# Quad_Mosfet_Module.net
KiCad netlist of a schematic drawn in EAGLE
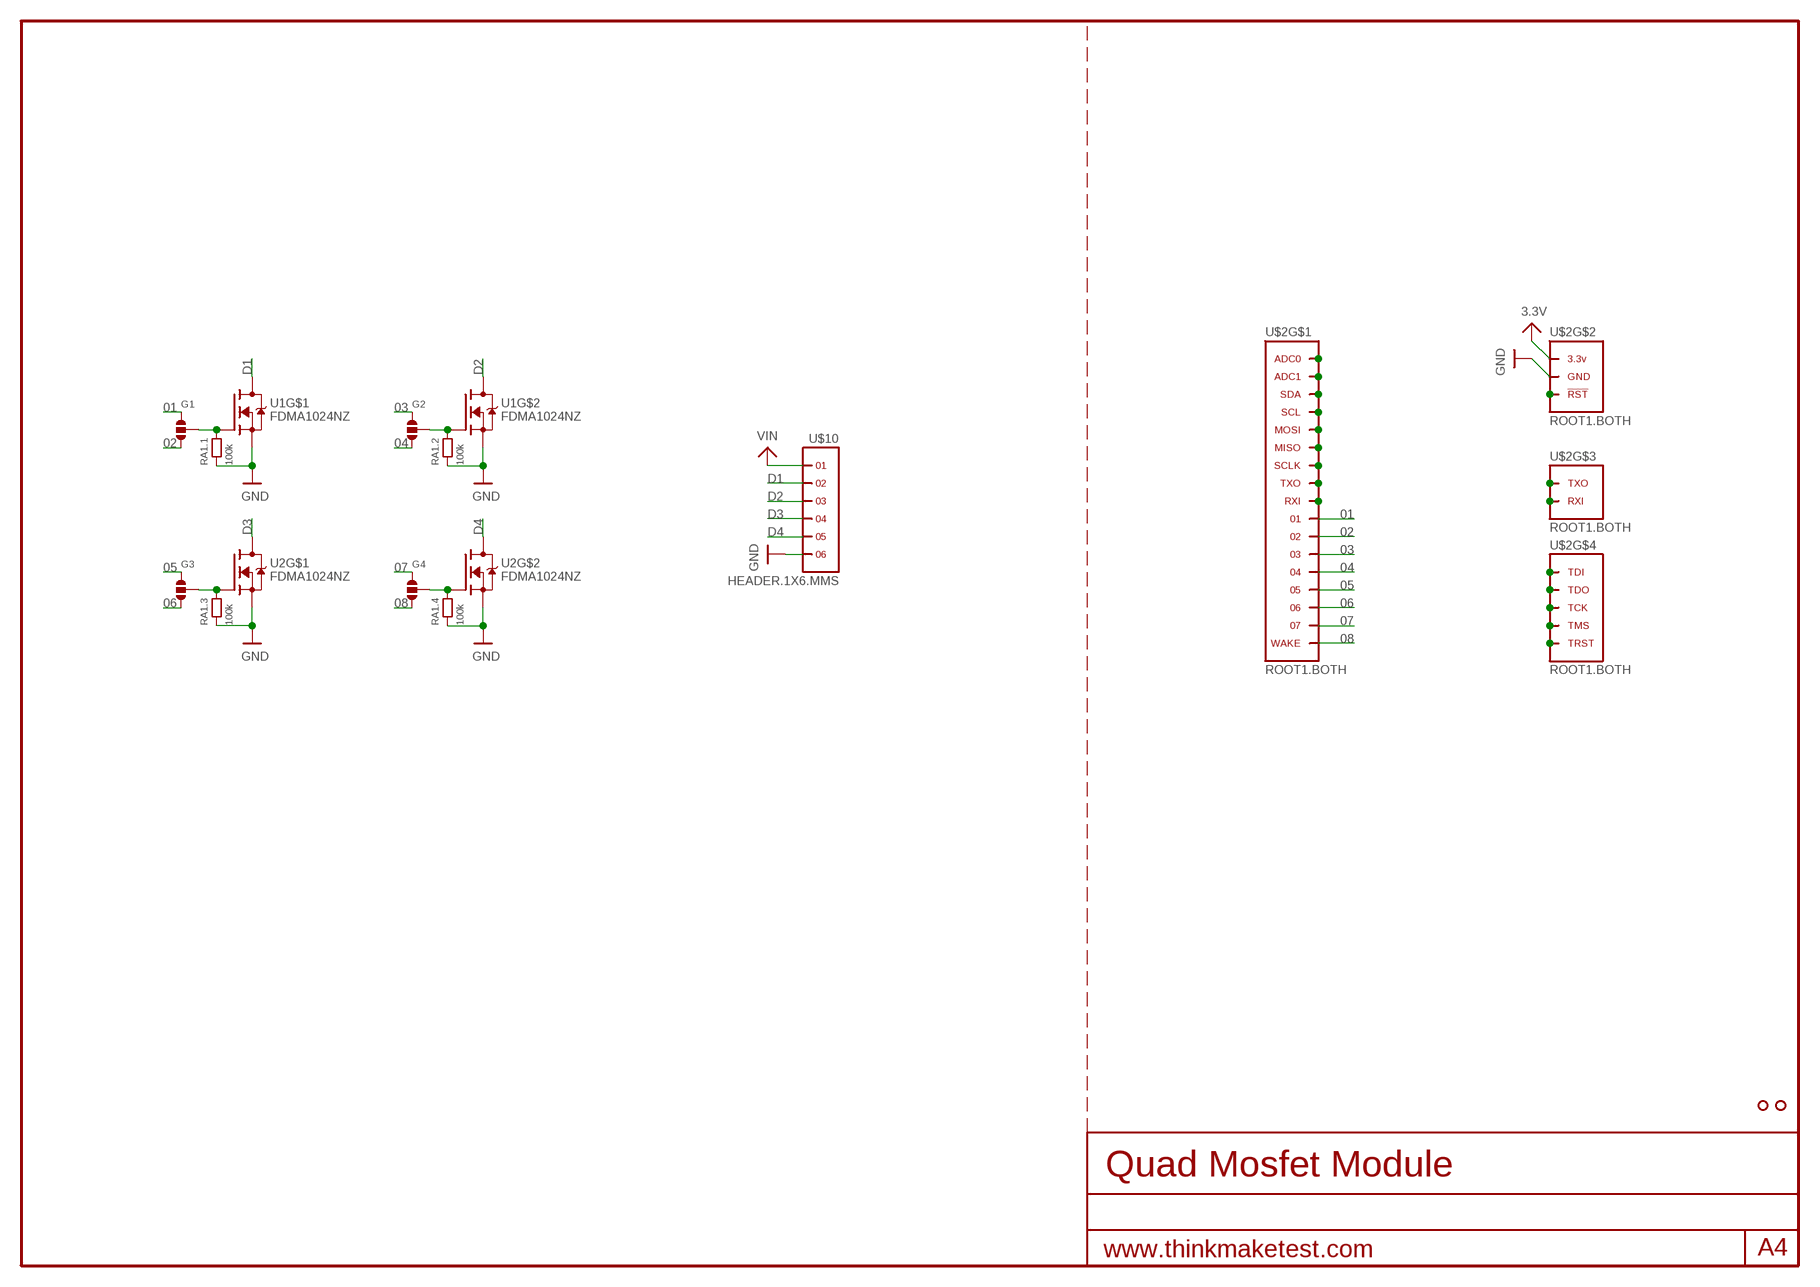
[diagram p0: schematic, sheet 1]

(export (version "E")
  (design (tool "Eeschema 10.0.6"))
  (components
    (comp (ref "G1")
      (value "SOLDERJUMPER.3.MED.12")
      (footprint "eagle-import:3.MED.12")
      (libsource (lib "eagle-import") (part "SOLDERJUMPER.3.MED.12"))
    )
    (comp (ref "G2")
      (value "SOLDERJUMPER.3.MED.12")
      (footprint "eagle-import:3.MED.12")
      (libsource (lib "eagle-import") (part "SOLDERJUMPER.3.MED.12"))
    )
    (comp (ref "G3")
      (value "SOLDERJUMPER.3.MED.12")
      (footprint "eagle-import:3.MED.12")
      (libsource (lib "eagle-import") (part "SOLDERJUMPER.3.MED.12"))
    )
    (comp (ref "G4")
      (value "SOLDERJUMPER.3.MED.12")
      (footprint "eagle-import:3.MED.12")
      (libsource (lib "eagle-import") (part "SOLDERJUMPER.3.MED.12"))
    )
    (comp (ref "RA1")
      (value "100k")
      (footprint "eagle-import:0603.4.C")
      (libsource (lib "eagle-import") (part "RA-4.0603"))
    )
    (comp (ref "U$2")
      (value "ROOT1.BOTH")
      (footprint "eagle-import:ROOT1.BOTH")
      (libsource (lib "eagle-import") (part "ROOT1.BOTH"))
    )
    (comp (ref "U$3")
      (value "HOLE.#2")
      (footprint "eagle-import:#2")
      (libsource (lib "eagle-import") (part "HOLE.#2"))
    )
    (comp (ref "U$4")
      (value "HOLE.#2")
      (footprint "eagle-import:#2")
      (libsource (lib "eagle-import") (part "HOLE.#2"))
    )
    (comp (ref "U$10")
      (value "HEADER.1X6.MMS")
      (footprint "eagle-import:MMS-106-02-X-SH")
      (libsource (lib "eagle-import") (part "HEADER.1X6.MMS"))
    )
    (comp (ref "U1")
      (value "FDMA1024NZ")
      (footprint "eagle-import:MICROFET-6")
      (libsource (lib "eagle-import") (part "FDMA1024NZ"))
    )
    (comp (ref "U2")
      (value "FDMA1024NZ")
      (footprint "eagle-import:MICROFET-6")
      (libsource (lib "eagle-import") (part "FDMA1024NZ"))
    )
  )
  (nets
    (net (code "1") (name "/01") (class "Default")
      (node (ref "G1") (pin "1") (pinfunction "1_1") (pintype "bidirectional"))
      (node (ref "U$2") (pin "01") (pinfunction "01_01") (pintype "bidirectional"))
      (node (ref "U$2") (pin "01@1") (pinfunction "01_01@1") (pintype "bidirectional"))
      (node (ref "U$2") (pin "01@VIA") (pinfunction "01_01@VIA") (pintype "bidirectional"))
    )
    (net (code "2") (name "/02") (class "Default")
      (node (ref "G1") (pin "3") (pinfunction "3_3") (pintype "bidirectional"))
      (node (ref "U$2") (pin "02") (pinfunction "02_02") (pintype "bidirectional"))
      (node (ref "U$2") (pin "02@1") (pinfunction "02_02@1") (pintype "bidirectional"))
      (node (ref "U$2") (pin "02@VIA") (pinfunction "02_02@VIA") (pintype "bidirectional"))
    )
    (net (code "3") (name "/03") (class "Default")
      (node (ref "G2") (pin "1") (pinfunction "1_1") (pintype "bidirectional"))
      (node (ref "U$2") (pin "03") (pinfunction "03_03") (pintype "bidirectional"))
      (node (ref "U$2") (pin "03@1") (pinfunction "03_03@1") (pintype "bidirectional"))
      (node (ref "U$2") (pin "03@VIA") (pinfunction "03_03@VIA") (pintype "bidirectional"))
    )
    (net (code "4") (name "/04") (class "Default")
      (node (ref "G2") (pin "3") (pinfunction "3_3") (pintype "bidirectional"))
      (node (ref "U$2") (pin "04") (pinfunction "04_04") (pintype "bidirectional"))
      (node (ref "U$2") (pin "04@1") (pinfunction "04_04@1") (pintype "bidirectional"))
      (node (ref "U$2") (pin "04@VIA") (pinfunction "04_04@VIA") (pintype "bidirectional"))
    )
    (net (code "5") (name "/05") (class "Default")
      (node (ref "G3") (pin "1") (pinfunction "1_1") (pintype "bidirectional"))
      (node (ref "U$2") (pin "05") (pinfunction "05_05") (pintype "bidirectional"))
      (node (ref "U$2") (pin "05@1") (pinfunction "05_05@1") (pintype "bidirectional"))
      (node (ref "U$2") (pin "05@VIA") (pinfunction "05_05@VIA") (pintype "bidirectional"))
    )
    (net (code "6") (name "/06") (class "Default")
      (node (ref "G3") (pin "3") (pinfunction "3_3") (pintype "bidirectional"))
      (node (ref "U$2") (pin "06") (pinfunction "06_06") (pintype "bidirectional"))
      (node (ref "U$2") (pin "06@1") (pinfunction "06_06@1") (pintype "bidirectional"))
      (node (ref "U$2") (pin "06@VIA") (pinfunction "06_06@VIA") (pintype "bidirectional"))
    )
    (net (code "7") (name "/07") (class "Default")
      (node (ref "G4") (pin "1") (pinfunction "1_1") (pintype "bidirectional"))
      (node (ref "U$2") (pin "07") (pinfunction "07_07") (pintype "bidirectional"))
      (node (ref "U$2") (pin "07@1") (pinfunction "07_07@1") (pintype "bidirectional"))
      (node (ref "U$2") (pin "07@VIA") (pinfunction "07_07@VIA") (pintype "bidirectional"))
    )
    (net (code "8") (name "/08") (class "Default")
      (node (ref "G4") (pin "3") (pinfunction "3_3") (pintype "bidirectional"))
      (node (ref "U$2") (pin "WAKE") (pinfunction "WAKE_WAKE") (pintype "bidirectional"))
      (node (ref "U$2") (pin "WAKE@1") (pinfunction "WAKE_WAKE@1") (pintype "bidirectional"))
      (node (ref "U$2") (pin "WAKE@VIA") (pinfunction "WAKE_WAKE@VIA") (pintype "bidirectional"))
    )
    (net (code "9") (name "/D1") (class "Default")
      (node (ref "U$10") (pin "2") (pinfunction "2_2") (pintype "bidirectional"))
      (node (ref "U$10") (pin "2@1") (pinfunction "2_2@1") (pintype "bidirectional"))
      (node (ref "U1") (pin "D1") (pinfunction "D_D1") (pintype "bidirectional"))
      (node (ref "U1") (pin "D1@PAD") (pinfunction "D_D1@PAD") (pintype "bidirectional"))
    )
    (net (code "10") (name "/D2") (class "Default")
      (node (ref "U$10") (pin "3") (pinfunction "3_3") (pintype "bidirectional"))
      (node (ref "U$10") (pin "3@1") (pinfunction "3_3@1") (pintype "bidirectional"))
      (node (ref "U1") (pin "D2") (pinfunction "D_D2") (pintype "bidirectional"))
      (node (ref "U1") (pin "D2@PAD") (pinfunction "D_D2@PAD") (pintype "bidirectional"))
    )
    (net (code "11") (name "/D3") (class "Default")
      (node (ref "U$10") (pin "4") (pinfunction "4_4") (pintype "bidirectional"))
      (node (ref "U$10") (pin "4@1") (pinfunction "4_4@1") (pintype "bidirectional"))
      (node (ref "U2") (pin "D1") (pinfunction "D_D1") (pintype "bidirectional"))
      (node (ref "U2") (pin "D1@PAD") (pinfunction "D_D1@PAD") (pintype "bidirectional"))
    )
    (net (code "12") (name "/D4") (class "Default")
      (node (ref "U$10") (pin "5") (pinfunction "5_5") (pintype "bidirectional"))
      (node (ref "U$10") (pin "5@1") (pinfunction "5_5@1") (pintype "bidirectional"))
      (node (ref "U2") (pin "D2") (pinfunction "D_D2") (pintype "bidirectional"))
      (node (ref "U2") (pin "D2@PAD") (pinfunction "D_D2@PAD") (pintype "bidirectional"))
    )
    (net (code "13") (name "3.3V") (class "Default")
      (node (ref "U$2") (pin "3.3V@1") (pinfunction "3.3V_3.3V@1") (pintype "bidirectional"))
      (node (ref "U$2") (pin "3.3V@10") (pinfunction "3.3V_3.3V@10") (pintype "bidirectional"))
      (node (ref "U$2") (pin "3.3V@11") (pinfunction "3.3V_3.3V@11") (pintype "bidirectional"))
      (node (ref "U$2") (pin "3.3V@12") (pinfunction "3.3V_3.3V@12") (pintype "bidirectional"))
      (node (ref "U$2") (pin "3.3V@13") (pinfunction "3.3V_3.3V@13") (pintype "bidirectional"))
      (node (ref "U$2") (pin "3.3V@14") (pinfunction "3.3V_3.3V@14") (pintype "bidirectional"))
      (node (ref "U$2") (pin "3.3V@15") (pinfunction "3.3V_3.3V@15") (pintype "bidirectional"))
      (node (ref "U$2") (pin "3.3V@16") (pinfunction "3.3V_3.3V@16") (pintype "bidirectional"))
      (node (ref "U$2") (pin "3.3V@17") (pinfunction "3.3V_3.3V@17") (pintype "bidirectional"))
      (node (ref "U$2") (pin "3.3V@18") (pinfunction "3.3V_3.3V@18") (pintype "bidirectional"))
      (node (ref "U$2") (pin "3.3V@19") (pinfunction "3.3V_3.3V@19") (pintype "bidirectional"))
      (node (ref "U$2") (pin "3.3V@2") (pinfunction "3.3V_3.3V@2") (pintype "bidirectional"))
      (node (ref "U$2") (pin "3.3V@20") (pinfunction "3.3V_3.3V@20") (pintype "bidirectional"))
      (node (ref "U$2") (pin "3.3V@21") (pinfunction "3.3V_3.3V@21") (pintype "bidirectional"))
      (node (ref "U$2") (pin "3.3V@22") (pinfunction "3.3V_3.3V@22") (pintype "bidirectional"))
      (node (ref "U$2") (pin "3.3V@23") (pinfunction "3.3V_3.3V@23") (pintype "bidirectional"))
      (node (ref "U$2") (pin "3.3V@24") (pinfunction "3.3V_3.3V@24") (pintype "bidirectional"))
      (node (ref "U$2") (pin "3.3V@3") (pinfunction "3.3V_3.3V@3") (pintype "bidirectional"))
      (node (ref "U$2") (pin "3.3V@4") (pinfunction "3.3V_3.3V@4") (pintype "bidirectional"))
      (node (ref "U$2") (pin "3.3V@5") (pinfunction "3.3V_3.3V@5") (pintype "bidirectional"))
      (node (ref "U$2") (pin "3.3V@6") (pinfunction "3.3V_3.3V@6") (pintype "bidirectional"))
      (node (ref "U$2") (pin "3.3V@7") (pinfunction "3.3V_3.3V@7") (pintype "bidirectional"))
      (node (ref "U$2") (pin "3.3V@8") (pinfunction "3.3V_3.3V@8") (pintype "bidirectional"))
      (node (ref "U$2") (pin "3.3V@9") (pinfunction "3.3V_3.3V@9") (pintype "bidirectional"))
      (node (ref "U$2") (pin "3.3V@VIA") (pinfunction "3.3V_3.3V@VIA") (pintype "bidirectional"))
    )
    (net (code "14") (name "GND") (class "Default")
      (node (ref "RA1") (pin "1") (pinfunction "1_1") (pintype "bidirectional"))
      (node (ref "RA1") (pin "3") (pinfunction "1_3") (pintype "bidirectional"))
      (node (ref "RA1") (pin "5") (pinfunction "1_5") (pintype "bidirectional"))
      (node (ref "RA1") (pin "7") (pinfunction "1_7") (pintype "bidirectional"))
      (node (ref "U$10") (pin "6") (pinfunction "6_6") (pintype "bidirectional"))
      (node (ref "U$10") (pin "6@1") (pinfunction "6_6@1") (pintype "bidirectional"))
      (node (ref "U$2") (pin "GND@1") (pinfunction "GND_GND@1") (pintype "bidirectional"))
      (node (ref "U$2") (pin "GND@10") (pinfunction "GND_GND@10") (pintype "bidirectional"))
      (node (ref "U$2") (pin "GND@11") (pinfunction "GND_GND@11") (pintype "bidirectional"))
      (node (ref "U$2") (pin "GND@12") (pinfunction "GND_GND@12") (pintype "bidirectional"))
      (node (ref "U$2") (pin "GND@13") (pinfunction "GND_GND@13") (pintype "bidirectional"))
      (node (ref "U$2") (pin "GND@14") (pinfunction "GND_GND@14") (pintype "bidirectional"))
      (node (ref "U$2") (pin "GND@15") (pinfunction "GND_GND@15") (pintype "bidirectional"))
      (node (ref "U$2") (pin "GND@16") (pinfunction "GND_GND@16") (pintype "bidirectional"))
      (node (ref "U$2") (pin "GND@17") (pinfunction "GND_GND@17") (pintype "bidirectional"))
      (node (ref "U$2") (pin "GND@18") (pinfunction "GND_GND@18") (pintype "bidirectional"))
      (node (ref "U$2") (pin "GND@19") (pinfunction "GND_GND@19") (pintype "bidirectional"))
      (node (ref "U$2") (pin "GND@2") (pinfunction "GND_GND@2") (pintype "bidirectional"))
      (node (ref "U$2") (pin "GND@20") (pinfunction "GND_GND@20") (pintype "bidirectional"))
      (node (ref "U$2") (pin "GND@21") (pinfunction "GND_GND@21") (pintype "bidirectional"))
      (node (ref "U$2") (pin "GND@22") (pinfunction "GND_GND@22") (pintype "bidirectional"))
      (node (ref "U$2") (pin "GND@23") (pinfunction "GND_GND@23") (pintype "bidirectional"))
      (node (ref "U$2") (pin "GND@24") (pinfunction "GND_GND@24") (pintype "bidirectional"))
      (node (ref "U$2") (pin "GND@25") (pinfunction "GND_GND@25") (pintype "bidirectional"))
      (node (ref "U$2") (pin "GND@26") (pinfunction "GND_GND@26") (pintype "bidirectional"))
      (node (ref "U$2") (pin "GND@3") (pinfunction "GND_GND@3") (pintype "bidirectional"))
      (node (ref "U$2") (pin "GND@4") (pinfunction "GND_GND@4") (pintype "bidirectional"))
      (node (ref "U$2") (pin "GND@5") (pinfunction "GND_GND@5") (pintype "bidirectional"))
      (node (ref "U$2") (pin "GND@6") (pinfunction "GND_GND@6") (pintype "bidirectional"))
      (node (ref "U$2") (pin "GND@7") (pinfunction "GND_GND@7") (pintype "bidirectional"))
      (node (ref "U$2") (pin "GND@8") (pinfunction "GND_GND@8") (pintype "bidirectional"))
      (node (ref "U$2") (pin "GND@9") (pinfunction "GND_GND@9") (pintype "bidirectional"))
      (node (ref "U$2") (pin "GND@VIA") (pinfunction "GND_GND@VIA") (pintype "bidirectional"))
      (node (ref "U1") (pin "S1") (pinfunction "S_S1") (pintype "bidirectional"))
      (node (ref "U1") (pin "S2") (pinfunction "S_S2") (pintype "bidirectional"))
      (node (ref "U2") (pin "S1") (pinfunction "S_S1") (pintype "bidirectional"))
      (node (ref "U2") (pin "S2") (pinfunction "S_S2") (pintype "bidirectional"))
    )
    (net (code "15") (name "Net-(RA1B-2)") (class "Default")
      (node (ref "G2") (pin "2") (pinfunction "2_2") (pintype "bidirectional"))
      (node (ref "RA1") (pin "4") (pinfunction "2_4") (pintype "bidirectional"))
      (node (ref "U1") (pin "G2") (pinfunction "G_G2") (pintype "bidirectional"))
    )
    (net (code "16") (name "Net-(RA1C-2)") (class "Default")
      (node (ref "G3") (pin "2") (pinfunction "2_2") (pintype "bidirectional"))
      (node (ref "RA1") (pin "6") (pinfunction "2_6") (pintype "bidirectional"))
      (node (ref "U2") (pin "G1") (pinfunction "G_G1") (pintype "bidirectional"))
    )
    (net (code "17") (name "Net-(RA1D-2)") (class "Default")
      (node (ref "G4") (pin "2") (pinfunction "2_2") (pintype "bidirectional"))
      (node (ref "RA1") (pin "8") (pinfunction "2_8") (pintype "bidirectional"))
      (node (ref "U2") (pin "G2") (pinfunction "G_G2") (pintype "bidirectional"))
    )
    (net (code "18") (name "Net-(U$2-PadADC0)") (class "Default")
      (node (ref "U$2") (pin "ADC0") (pinfunction "ADC0_ADC0") (pintype "bidirectional"))
      (node (ref "U$2") (pin "ADC0@1") (pinfunction "ADC0_ADC0@1") (pintype "bidirectional"))
      (node (ref "U$2") (pin "ADC0@VIA") (pinfunction "ADC0_ADC0@VIA") (pintype "bidirectional"))
    )
    (net (code "19") (name "Net-(U$2-PadADC1)") (class "Default")
      (node (ref "U$2") (pin "ADC1") (pinfunction "ADC1_ADC1") (pintype "bidirectional"))
      (node (ref "U$2") (pin "ADC1@1") (pinfunction "ADC1_ADC1@1") (pintype "bidirectional"))
      (node (ref "U$2") (pin "ADC1@VIA") (pinfunction "ADC1_ADC1@VIA") (pintype "bidirectional"))
    )
    (net (code "20") (name "Net-(U$2-PadMISO)") (class "Default")
      (node (ref "U$2") (pin "MISO") (pinfunction "MISO_MISO") (pintype "bidirectional"))
      (node (ref "U$2") (pin "MISO@1") (pinfunction "MISO_MISO@1") (pintype "bidirectional"))
      (node (ref "U$2") (pin "MISO@VIA") (pinfunction "MISO_MISO@VIA") (pintype "bidirectional"))
    )
    (net (code "21") (name "Net-(U$2-PadMOSI)") (class "Default")
      (node (ref "U$2") (pin "MOSI") (pinfunction "MOSI_MOSI") (pintype "bidirectional"))
      (node (ref "U$2") (pin "MOSI@1") (pinfunction "MOSI_MOSI@1") (pintype "bidirectional"))
      (node (ref "U$2") (pin "MOSI@VIA") (pinfunction "MOSI_MOSI@VIA") (pintype "bidirectional"))
    )
    (net (code "22") (name "Net-(U$2-PadRXI)") (class "Default")
      (node (ref "U$2") (pin "RXI") (pinfunction "RXI_RXI") (pintype "bidirectional"))
      (node (ref "U$2") (pin "RXI@1") (pinfunction "RXI_RXI@1") (pintype "bidirectional"))
      (node (ref "U$2") (pin "RXI@VIA") (pinfunction "RXI_RXI@VIA") (pintype "bidirectional"))
    )
    (net (code "23") (name "Net-(U$2-PadSCL)") (class "Default")
      (node (ref "U$2") (pin "SCL") (pinfunction "SCL_SCL") (pintype "bidirectional"))
      (node (ref "U$2") (pin "SCL@1") (pinfunction "SCL_SCL@1") (pintype "bidirectional"))
      (node (ref "U$2") (pin "SCL@VIA") (pinfunction "SCL_SCL@VIA") (pintype "bidirectional"))
    )
    (net (code "24") (name "Net-(U$2-PadSCLK)") (class "Default")
      (node (ref "U$2") (pin "SCLK") (pinfunction "SCLK_SCLK") (pintype "bidirectional"))
      (node (ref "U$2") (pin "SCLK@1") (pinfunction "SCLK_SCLK@1") (pintype "bidirectional"))
      (node (ref "U$2") (pin "SCLK@VIA") (pinfunction "SCLK_SCLK@VIA") (pintype "bidirectional"))
    )
    (net (code "25") (name "Net-(U$2-PadSDA)") (class "Default")
      (node (ref "U$2") (pin "SDA") (pinfunction "SDA_SDA") (pintype "bidirectional"))
      (node (ref "U$2") (pin "SDA@1") (pinfunction "SDA_SDA@1") (pintype "bidirectional"))
      (node (ref "U$2") (pin "SDA@VIA") (pinfunction "SDA_SDA@VIA") (pintype "bidirectional"))
    )
    (net (code "26") (name "Net-(U$2-PadTCK)") (class "Default")
      (node (ref "U$2") (pin "TCK") (pinfunction "TCK_TCK") (pintype "bidirectional"))
      (node (ref "U$2") (pin "TCK@1") (pinfunction "TCK_TCK@1") (pintype "bidirectional"))
      (node (ref "U$2") (pin "TCK@VIA") (pinfunction "TCK_TCK@VIA") (pintype "bidirectional"))
    )
    (net (code "27") (name "Net-(U$2-PadTDI)") (class "Default")
      (node (ref "U$2") (pin "TDI") (pinfunction "TDI_TDI") (pintype "bidirectional"))
      (node (ref "U$2") (pin "TDI@1") (pinfunction "TDI_TDI@1") (pintype "bidirectional"))
      (node (ref "U$2") (pin "TDI@VIA") (pinfunction "TDI_TDI@VIA") (pintype "bidirectional"))
    )
    (net (code "28") (name "Net-(U$2-PadTDO)") (class "Default")
      (node (ref "U$2") (pin "TDO") (pinfunction "TDO_TDO") (pintype "bidirectional"))
      (node (ref "U$2") (pin "TDO@1") (pinfunction "TDO_TDO@1") (pintype "bidirectional"))
      (node (ref "U$2") (pin "TDO@VIA") (pinfunction "TDO_TDO@VIA") (pintype "bidirectional"))
    )
    (net (code "29") (name "Net-(U$2-PadTMS)") (class "Default")
      (node (ref "U$2") (pin "TMS") (pinfunction "TMS_TMS") (pintype "bidirectional"))
      (node (ref "U$2") (pin "TMS@1") (pinfunction "TMS_TMS@1") (pintype "bidirectional"))
      (node (ref "U$2") (pin "TMS@VIA") (pinfunction "TMS_TMS@VIA") (pintype "bidirectional"))
    )
    (net (code "30") (name "Net-(U$2-PadTRST)") (class "Default")
      (node (ref "U$2") (pin "TRST") (pinfunction "TRST_TRST") (pintype "bidirectional"))
      (node (ref "U$2") (pin "TRST@1") (pinfunction "TRST_TRST@1") (pintype "bidirectional"))
      (node (ref "U$2") (pin "TRST@VIA") (pinfunction "TRST_TRST@VIA") (pintype "bidirectional"))
    )
    (net (code "31") (name "Net-(U$2-PadTXO)") (class "Default")
      (node (ref "U$2") (pin "TXO") (pinfunction "TXO_TXO") (pintype "bidirectional"))
      (node (ref "U$2") (pin "TXO@1") (pinfunction "TXO_TXO@1") (pintype "bidirectional"))
      (node (ref "U$2") (pin "TXO@VIA") (pinfunction "TXO_TXO@VIA") (pintype "bidirectional"))
    )
    (net (code "32") (name "Net-(U$2B-~{RST}-PadRST)") (class "Default")
      (node (ref "U$2") (pin "RST") (pinfunction "~{RST}_RST") (pintype "bidirectional"))
      (node (ref "U$2") (pin "RST@1") (pinfunction "~{RST}_RST@1") (pintype "bidirectional"))
      (node (ref "U$2") (pin "RST@VIA") (pinfunction "~{RST}_RST@VIA") (pintype "bidirectional"))
    )
    (net (code "33") (name "Net-(U$2C-RXI-PadRXI.DBG)") (class "Default")
      (node (ref "U$2") (pin "RXI.DBG") (pinfunction "RXI_RXI.DBG") (pintype "bidirectional"))
      (node (ref "U$2") (pin "RXI.DBG@1") (pinfunction "RXI_RXI.DBG@1") (pintype "bidirectional"))
      (node (ref "U$2") (pin "RXI.DBG@VIA") (pinfunction "RXI_RXI.DBG@VIA") (pintype "bidirectional"))
    )
    (net (code "34") (name "Net-(U$2C-TXO-PadTXO.DBG)") (class "Default")
      (node (ref "U$2") (pin "TXO.DBG") (pinfunction "TXO_TXO.DBG") (pintype "bidirectional"))
      (node (ref "U$2") (pin "TXO.DBG@1") (pinfunction "TXO_TXO.DBG@1") (pintype "bidirectional"))
      (node (ref "U$2") (pin "TXO.DBG@VIA") (pinfunction "TXO_TXO.DBG@VIA") (pintype "bidirectional"))
    )
    (net (code "35") (name "Net-(U1A-G)") (class "Default")
      (node (ref "G1") (pin "2") (pinfunction "2_2") (pintype "bidirectional"))
      (node (ref "RA1") (pin "2") (pinfunction "2_2") (pintype "bidirectional"))
      (node (ref "U1") (pin "G1") (pinfunction "G_G1") (pintype "bidirectional"))
    )
    (net (code "36") (name "VIN") (class "Default")
      (node (ref "U$10") (pin "1") (pinfunction "1_1") (pintype "bidirectional"))
      (node (ref "U$10") (pin "1@1") (pinfunction "1_1@1") (pintype "bidirectional"))
    )
  )
)
